# HDMI.net
KiCad netlist of a schematic drawn in Altium Designer
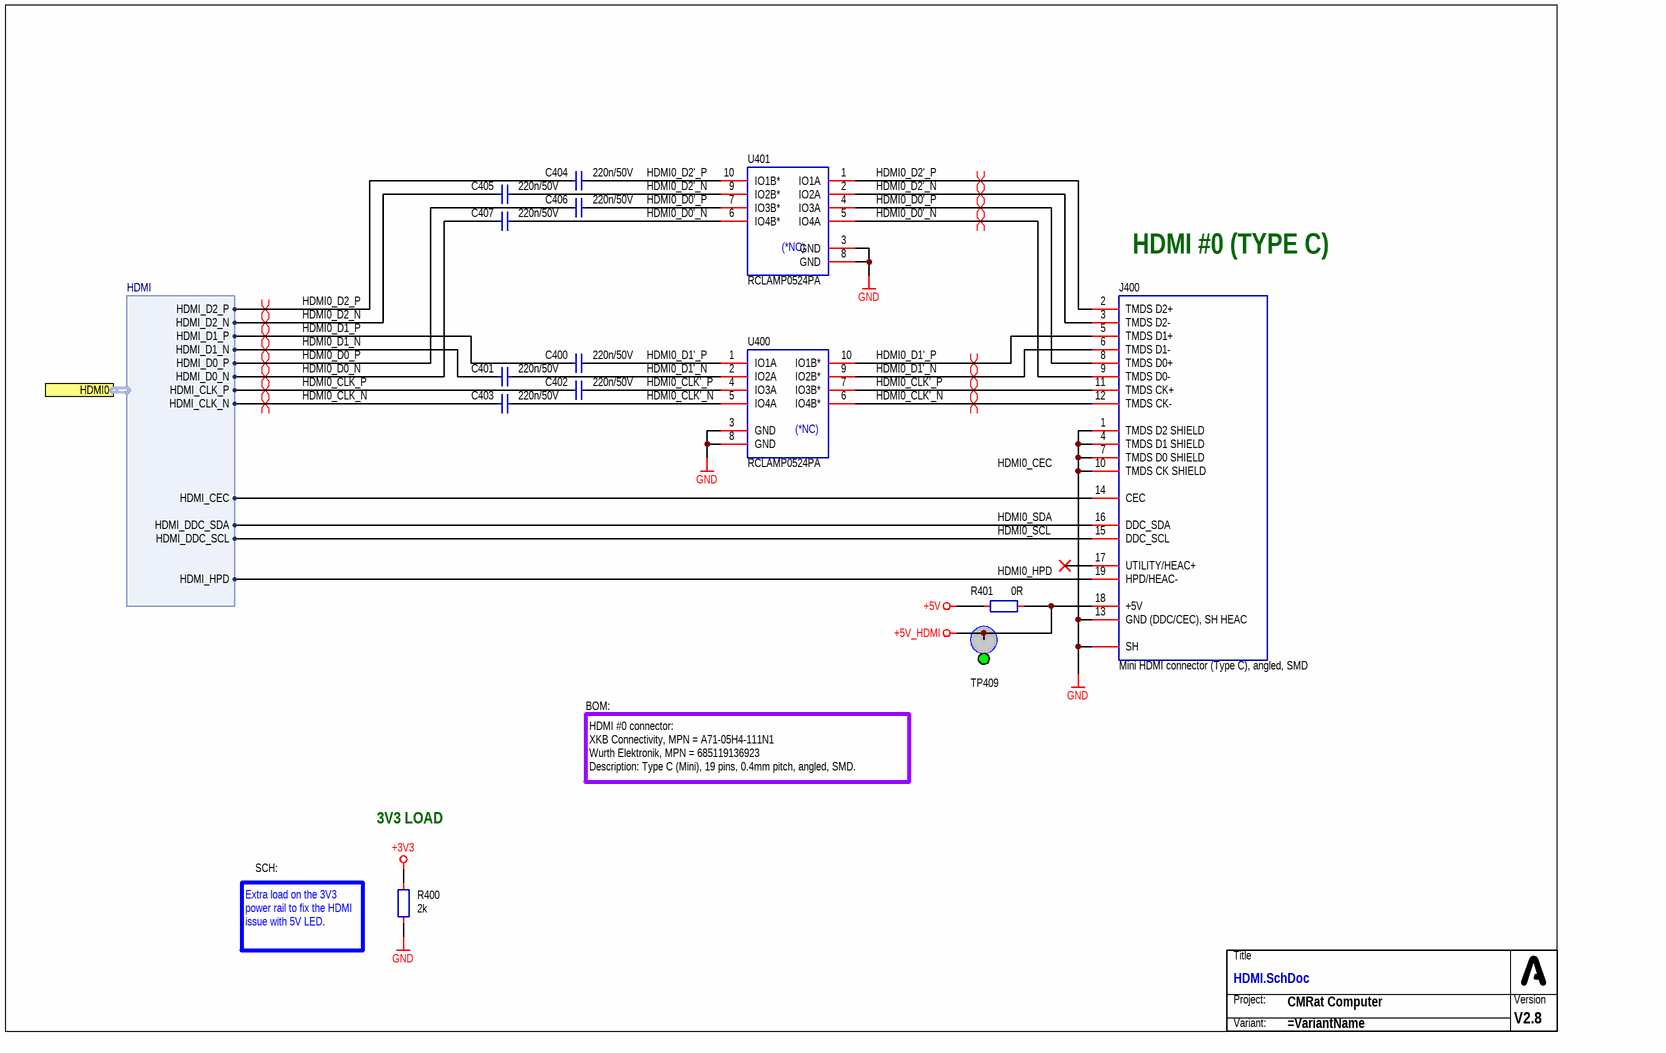
[diagram p0: HDMI.SchDoc]

(export (version "E")
  (design (tool "Eeschema 10.0.6"))
  (components
    (comp (ref "C400")
      (value "220n/50V")
      (footprint "CAP_0402_R")
      (description "CAP SMD 220n/50V ±10% 50V X5R (0402)")
      (fields (field (name "MANUFACTURER") "Murata Electronics") (field (name "MPN") "GRM155R61H224KE01D"))
      (libsource (lib "DB_DBLIB") (part "CAP"))
    )
    (comp (ref "C401")
      (value "220n/50V")
      (footprint "CAP_0402_R")
      (description "CAP SMD 220n/50V ±10% 50V X5R (0402)")
      (fields (field (name "MANUFACTURER") "Murata Electronics") (field (name "MPN") "GRM155R61H224KE01D"))
      (libsource (lib "DB_DBLIB") (part "CAP"))
    )
    (comp (ref "C402")
      (value "220n/50V")
      (footprint "CAP_0402_R")
      (description "CAP SMD 220n/50V ±10% 50V X5R (0402)")
      (fields (field (name "MANUFACTURER") "Murata Electronics") (field (name "MPN") "GRM155R61H224KE01D"))
      (libsource (lib "DB_DBLIB") (part "CAP"))
    )
    (comp (ref "C403")
      (value "220n/50V")
      (footprint "CAP_0402_R")
      (description "CAP SMD 220n/50V ±10% 50V X5R (0402)")
      (fields (field (name "MANUFACTURER") "Murata Electronics") (field (name "MPN") "GRM155R61H224KE01D"))
      (libsource (lib "DB_DBLIB") (part "CAP"))
    )
    (comp (ref "C404")
      (value "220n/50V")
      (footprint "CAP_0402_R")
      (description "CAP SMD 220n/50V ±10% 50V X5R (0402)")
      (fields (field (name "MANUFACTURER") "Murata Electronics") (field (name "MPN") "GRM155R61H224KE01D"))
      (libsource (lib "DB_DBLIB") (part "CAP"))
    )
    (comp (ref "C405")
      (value "220n/50V")
      (footprint "CAP_0402_R")
      (description "CAP SMD 220n/50V ±10% 50V X5R (0402)")
      (fields (field (name "MANUFACTURER") "Murata Electronics") (field (name "MPN") "GRM155R61H224KE01D"))
      (libsource (lib "DB_DBLIB") (part "CAP"))
    )
    (comp (ref "C406")
      (value "220n/50V")
      (footprint "CAP_0402_R")
      (description "CAP SMD 220n/50V ±10% 50V X5R (0402)")
      (fields (field (name "MANUFACTURER") "Murata Electronics") (field (name "MPN") "GRM155R61H224KE01D"))
      (libsource (lib "DB_DBLIB") (part "CAP"))
    )
    (comp (ref "C407")
      (value "220n/50V")
      (footprint "CAP_0402_R")
      (description "CAP SMD 220n/50V ±10% 50V X5R (0402)")
      (fields (field (name "MANUFACTURER") "Murata Electronics") (field (name "MPN") "GRM155R61H224KE01D"))
      (libsource (lib "DB_DBLIB") (part "CAP"))
    )
    (comp (ref "J400")
      (value "Mini HDMI connector (Type C), angled, SMD")
      (footprint "CON_XKB_A71-05H4-1X1N1")
      (description "Connector; HDMI v1.4+; Type C (Mini-HDMI);")
      (fields (field (name "MANUFACTURER") "XKB Connectivity") (field (name "MPN") "A71-05H4-111N1"))
      (libsource (lib "Pineberry_Lib") (part "CON_HDMI_1.4+_MINI_TYPE_C_A1"))
    )
    (comp (ref "R400")
      (value "2k")
      (footprint "RES_0603_R")
      (description "Resistor; Thick Film; 2k2; 1%; 100mW; 100PPM; 75V; Standard; SMD; 0603 (1608);")
      (fields (field (name "MANUFACTURER") "UNI-ROYAL(Uniroyal Elec)") (field (name "MPN") "0603WAF2001T5E"))
      (libsource (lib "") (part "RES_1"))
    )
    (comp (ref "R401")
      (value "0R")
      (footprint "RES_0603_R")
      (description "Resistor; Thick Film; 0R; SMD; 0603 (1608);")
      (fields (field (name "MANUFACTURER") "UNI-ROYAL(Uniroyal Elec)") (field (name "MPN") "0603WAF0000T5E"))
      (libsource (lib "MirFol_db_local") (part "RES"))
    )
    (comp (ref "TB400") (value "~") (libsource (lib "Symbols_NO_BOM") (part "SCH_TITLE_BLOCK_SIMPLE_NODATE")))
    (comp (ref "TP409")
      (value "ICT")
      (footprint "PCB_TP_ICT_100")
      (description "Test Point (ICT)")
      (libsource (lib "MirFol_lib") (part "PCB_TP_ICT"))
    )
    (comp (ref "U400")
      (value "RCLAMP0524PA")
      (footprint "ICC_SLP2510P8_250X100X60_P50_R")
      (description "IC; TVS Arrays; ESD Protection; 4-Channel; 17kV Air; 12kV Contact; 0.3pF Capitance; TBD; SMD; TBD;")
      (fields (field (name "MANUFACTURER") "Semtech Corporation") (field (name "MPN") "RCLAMP0524PATCT"))
      (libsource (lib "") (part "ICC_SMT_RCLAMP0524PA_1"))
    )
    (comp (ref "U401")
      (value "RCLAMP0524PA")
      (footprint "ICC_SLP2510P8_250X100X60_P50_R")
      (description "IC; TVS Arrays; ESD Protection; 4-Channel; 17kV Air; 12kV Contact; 0.3pF Capitance; TBD; SMD; TBD;")
      (fields (field (name "MANUFACTURER") "Semtech Corporation") (field (name "MPN") "RCLAMP0524PATCT"))
      (libsource (lib "MirFol_db_local") (part "ICC_SMT_RCLAMP0524PA"))
    )
  )
  (nets
    (net (code "2") (name "+3V3") (class "Default")
      (node (ref "R400") (pin "2") (pinfunction "2_2") (pintype "passive"))
    )
    (net (code "3") (name "+5V") (class "Default")
      (node (ref "R401") (pin "2") (pinfunction "2_2") (pintype "passive"))
    )
    (net (code "4") (name "+5V_HDMI") (class "Default")
      (node (ref "J400") (pin "18") (pinfunction "+5V_18") (pintype "passive"))
      (node (ref "R401") (pin "1") (pinfunction "1_1") (pintype "passive"))
      (node (ref "TP409") (pin "1") (pinfunction "1_1") (pintype "passive"))
    )
    (net (code "6") (name "/HDMI0_CLK'_N") (class "Default")
      (node (ref "C403") (pin "2") (pintype "passive"))
      (node (ref "J400") (pin "12") (pinfunction "TMDS_CK-_12") (pintype "passive"))
      (node (ref "U400") (pin "5") (pinfunction "IO4A_5") (pintype "passive"))
      (node (ref "U400") (pin "6") (pinfunction "IO4B*_6") (pintype "passive"))
    )
    (net (code "7") (name "/HDMI0_CLK'_P") (class "Default")
      (node (ref "C402") (pin "2") (pintype "passive"))
      (node (ref "J400") (pin "11") (pinfunction "TMDS_CK+_11") (pintype "passive"))
      (node (ref "U400") (pin "4") (pinfunction "IO3A_4") (pintype "passive"))
      (node (ref "U400") (pin "7") (pinfunction "IO3B*_7") (pintype "passive"))
    )
    (net (code "8") (name "/HDMI0_CLK_N") (class "Default") (node (ref "C403") (pin "1") (pintype "passive")))
    (net (code "9") (name "/HDMI0_CLK_P") (class "Default") (node (ref "C402") (pin "1") (pintype "passive")))
    (net (code "10") (name "/HDMI0_D0'_N") (class "Default")
      (node (ref "C407") (pin "2") (pintype "passive"))
      (node (ref "J400") (pin "9") (pinfunction "TMDS_D0-_9") (pintype "passive"))
      (node (ref "U401") (pin "5") (pinfunction "IO4A_5") (pintype "passive"))
      (node (ref "U401") (pin "6") (pinfunction "IO4B*_6") (pintype "passive"))
    )
    (net (code "11") (name "/HDMI0_D0'_P") (class "Default")
      (node (ref "C406") (pin "2") (pintype "passive"))
      (node (ref "J400") (pin "8") (pinfunction "TMDS_D0+_8") (pintype "passive"))
      (node (ref "U401") (pin "4") (pinfunction "IO3A_4") (pintype "passive"))
      (node (ref "U401") (pin "7") (pinfunction "IO3B*_7") (pintype "passive"))
    )
    (net (code "12") (name "/HDMI0_D0_N") (class "Default") (node (ref "C407") (pin "1") (pintype "passive")))
    (net (code "13") (name "/HDMI0_D0_P") (class "Default") (node (ref "C406") (pin "1") (pintype "passive")))
    (net (code "14") (name "/HDMI0_D1'_N") (class "Default")
      (node (ref "C401") (pin "2") (pintype "passive"))
      (node (ref "J400") (pin "6") (pinfunction "TMDS_D1-_6") (pintype "passive"))
      (node (ref "U400") (pin "2") (pinfunction "IO2A_2") (pintype "passive"))
      (node (ref "U400") (pin "9") (pinfunction "IO2B*_9") (pintype "passive"))
    )
    (net (code "15") (name "/HDMI0_D1'_P") (class "Default")
      (node (ref "C400") (pin "2") (pintype "passive"))
      (node (ref "J400") (pin "5") (pinfunction "TMDS_D1+_5") (pintype "passive"))
      (node (ref "U400") (pin "1") (pinfunction "IO1A_1") (pintype "passive"))
      (node (ref "U400") (pin "10") (pinfunction "IO1B*_10") (pintype "passive"))
    )
    (net (code "16") (name "/HDMI0_D1_N") (class "Default") (node (ref "C401") (pin "1") (pintype "passive")))
    (net (code "17") (name "/HDMI0_D1_P") (class "Default") (node (ref "C400") (pin "1") (pintype "passive")))
    (net (code "18") (name "/HDMI0_D2'_N") (class "Default")
      (node (ref "C405") (pin "2") (pintype "passive"))
      (node (ref "J400") (pin "3") (pinfunction "TMDS_D2-_3") (pintype "passive"))
      (node (ref "U401") (pin "2") (pinfunction "IO2A_2") (pintype "passive"))
      (node (ref "U401") (pin "9") (pinfunction "IO2B*_9") (pintype "passive"))
    )
    (net (code "19") (name "/HDMI0_D2'_P") (class "Default")
      (node (ref "C404") (pin "2") (pintype "passive"))
      (node (ref "J400") (pin "2") (pinfunction "TMDS_D2+_2") (pintype "passive"))
      (node (ref "U401") (pin "1") (pinfunction "IO1A_1") (pintype "passive"))
      (node (ref "U401") (pin "10") (pinfunction "IO1B*_10") (pintype "passive"))
    )
    (net (code "20") (name "/HDMI0_D2_N") (class "Default") (node (ref "C405") (pin "1") (pintype "passive")))
    (net (code "21") (name "/HDMI0_D2_P") (class "Default") (node (ref "C404") (pin "1") (pintype "passive")))
    (net (code "22") (name "/HDMI0_HPD") (class "Default")
      (node (ref "J400") (pin "19") (pinfunction "HPD/HEAC-_19") (pintype "passive"))
    )
    (net (code "23") (name "/HDMI0_SCL") (class "Default")
      (node (ref "J400") (pin "15") (pinfunction "DDC_SCL_15") (pintype "passive"))
    )
    (net (code "24") (name "/HDMI0_SDA") (class "Default")
      (node (ref "J400") (pin "16") (pinfunction "DDC_SDA_16") (pintype "passive"))
    )
    (net (code "25") (name "/HDMI_CEC") (class "Default")
      (node (ref "J400") (pin "14") (pinfunction "CEC_14") (pintype "passive"))
    )
    (net (code "27") (name "GND") (class "Default")
      (node (ref "J400") (pin "1") (pinfunction "TMDS_D2_SHIELD_1") (pintype "passive"))
      (node (ref "J400") (pin "10") (pinfunction "TMDS_CK_SHIELD_10") (pintype "passive"))
      (node (ref "J400") (pin "13") (pinfunction "GND_(DDC/CEC),_SH_HEAC_13") (pintype "passive"))
      (node (ref "J400") (pin "4") (pinfunction "TMDS_D1_SHIELD_4") (pintype "passive"))
      (node (ref "J400") (pin "7") (pinfunction "TMDS_D0_SHIELD_7") (pintype "passive"))
      (node (ref "J400") (pin "SH") (pinfunction "SH_SH") (pintype "passive"))
      (node (ref "R400") (pin "1") (pinfunction "1_1") (pintype "passive"))
      (node (ref "U400") (pin "3") (pinfunction "GND_3") (pintype "power_in"))
      (node (ref "U400") (pin "8") (pinfunction "GND_8") (pintype "power_in"))
      (node (ref "U401") (pin "3") (pinfunction "GND_3") (pintype "power_in"))
      (node (ref "U401") (pin "8") (pinfunction "GND_8") (pintype "power_in"))
    )
    (net (code "28") (name "unconnected-(J400-UTILITY{slash}HEAC+-Pad17)") (class "Default")
      (node (ref "J400") (pin "17") (pinfunction "UTILITY/HEAC+_17") (pintype "passive+no_connect"))
    )
  )
)
